# power_PCB.net
KiCad netlist of a schematic drawn in EAGLE
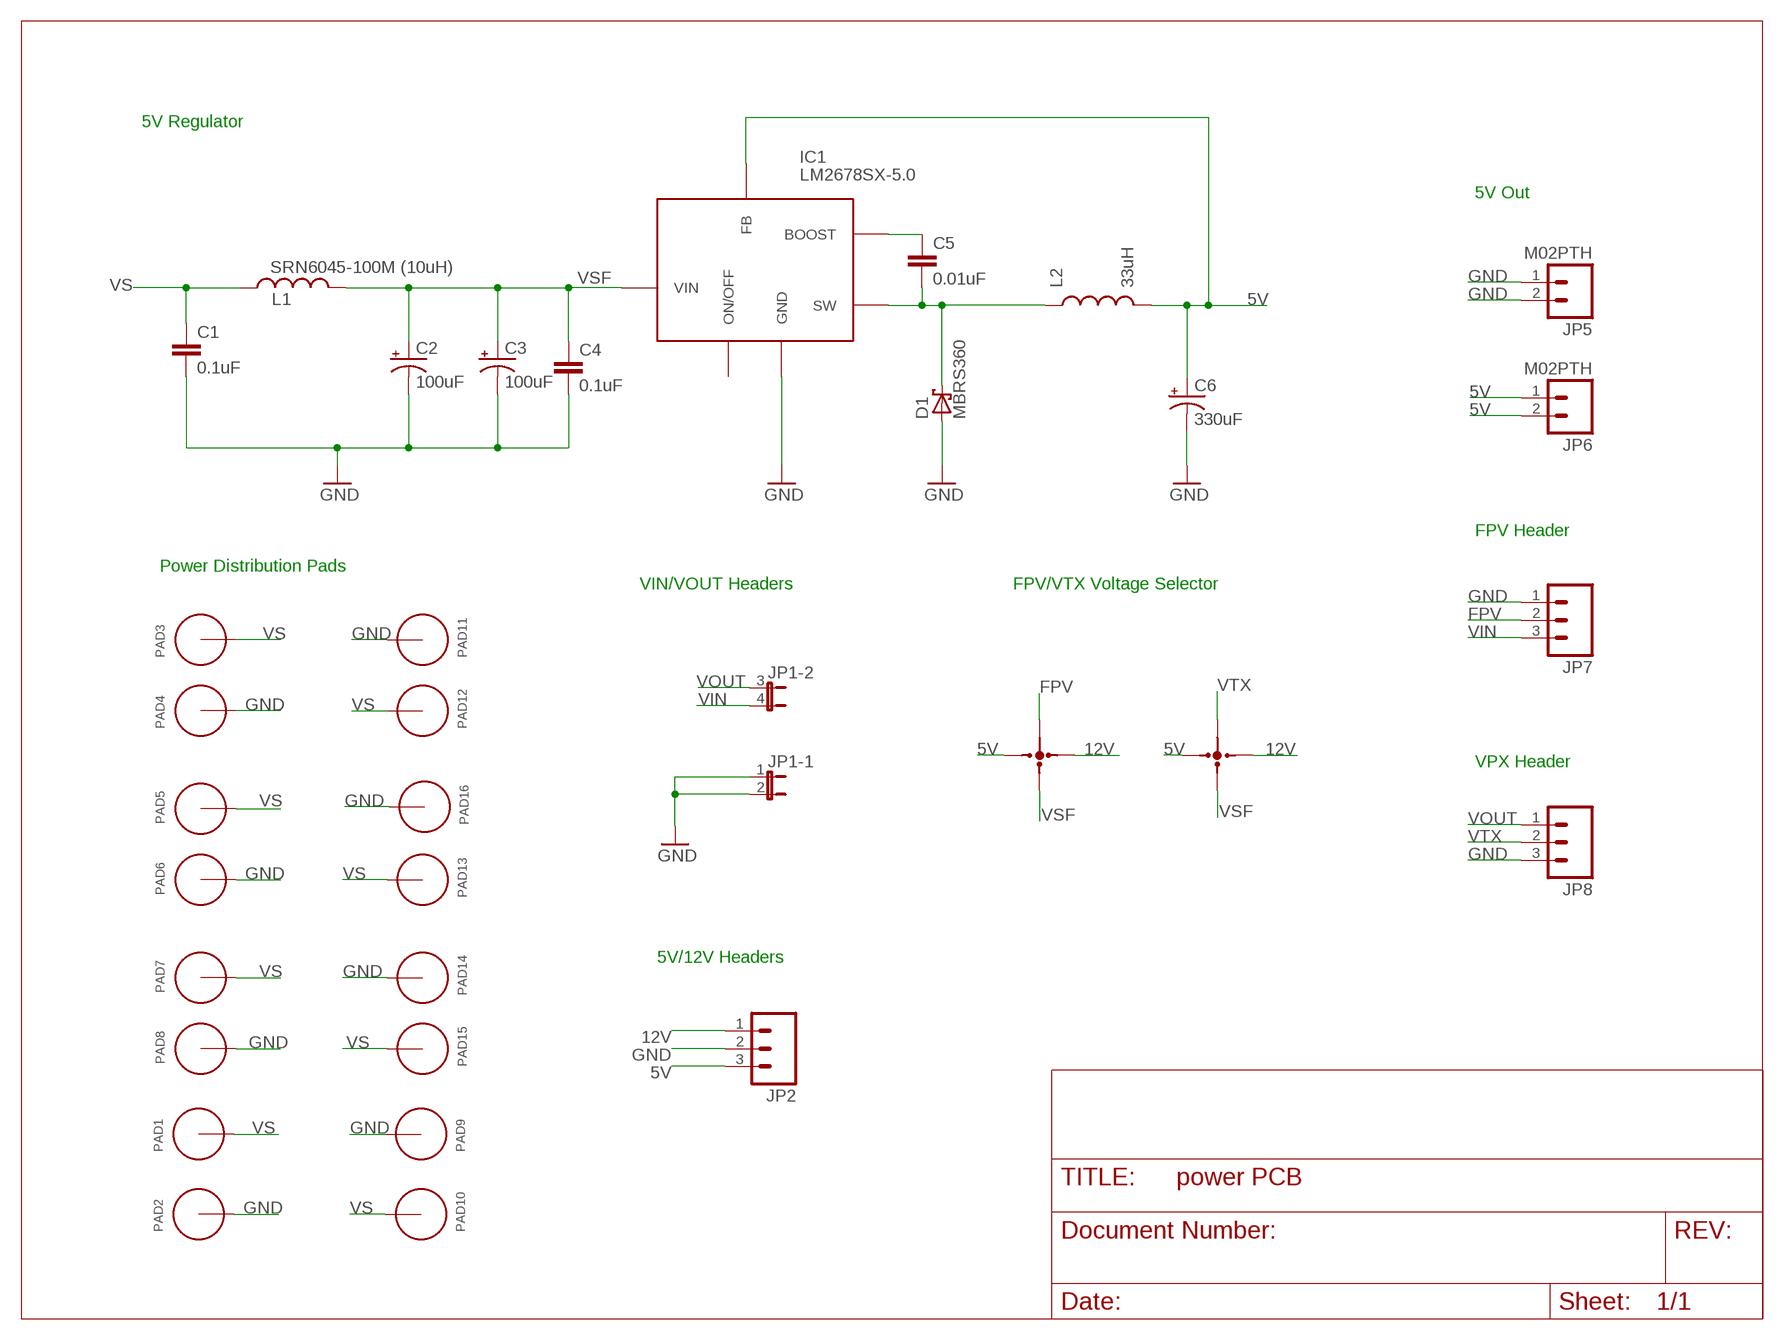
[diagram p0: schematic, sheet 1]

(export (version "E")
  (design (tool "Eeschema 10.0.6"))
  (components
    (comp (ref "C1")
      (value "0.1uF")
      (footprint "eagle-import:0603-CAP")
      (fields (field (name "PROD_ID") "CAP-00810"))
      (libsource (lib "eagle-import") (part "0.1UF-25V(+80/-20%)(0603)"))
    )
    (comp (ref "C2")
      (value "100uF")
      (footprint "eagle-import:EIA7343")
      (libsource (lib "eagle-import") (part "100UF-10V-10%(TANT)"))
    )
    (comp (ref "C3")
      (value "100uF")
      (footprint "eagle-import:EIA7343")
      (libsource (lib "eagle-import") (part "100UF-10V-10%(TANT)"))
    )
    (comp (ref "C4")
      (value "0.1uF")
      (footprint "eagle-import:0603-CAP")
      (libsource (lib "eagle-import") (part "0.1UF-25V(+80/-20%)(0603)"))
    )
    (comp (ref "C5")
      (value "0.01uF")
      (footprint "eagle-import:0603-CAP")
      (libsource (lib "eagle-import") (part "0.1UF-25V(+80/-20%)(0603)"))
    )
    (comp (ref "C6")
      (value "330uF")
      (footprint "eagle-import:EIA7343")
      (libsource (lib "eagle-import") (part "SparkFun-Capacitors_100UF-10V-10%(TANT)"))
    )
    (comp (ref "D1")
      (value "MBRS360")
      (footprint "eagle-import:SMB")
      (libsource (lib "eagle-import") (part "MBRS130LT3"))
    )
    (comp (ref "IC1")
      (value "LM2678SX-5.0")
      (footprint "eagle-import:P-TO263-7-1")
      (libsource (lib "eagle-import") (part "LM2678DX-5.0SX-5.0"))
    )
    (comp (ref "JP1")
      (value "JP2QE")
      (footprint "eagle-import:JP2Q")
      (libsource (lib "eagle-import") (part "JP2QE"))
    )
    (comp (ref "JP2")
      (value "M03PTH")
      (footprint "eagle-import:1X03")
      (libsource (lib "eagle-import") (part "M03PTH"))
    )
    (comp (ref "JP3")
      (value "3WAY_SMD_JUMPER")
      (footprint "eagle-import:3WAY_JUMPER")
      (libsource (lib "eagle-import") (part "3WAY_SMD_JUMPER"))
    )
    (comp (ref "JP4")
      (value "3WAY_SMD_JUMPER")
      (footprint "eagle-import:3WAY_JUMPER")
      (libsource (lib "eagle-import") (part "3WAY_SMD_JUMPER"))
    )
    (comp (ref "JP5")
      (value "M02PTH")
      (footprint "eagle-import:1X02")
      (libsource (lib "eagle-import") (part "M02PTH"))
    )
    (comp (ref "JP6")
      (value "M02PTH")
      (footprint "eagle-import:1X02")
      (libsource (lib "eagle-import") (part "M02PTH"))
    )
    (comp (ref "JP7")
      (value "M03PTH")
      (footprint "eagle-import:1X03")
      (libsource (lib "eagle-import") (part "M03PTH"))
    )
    (comp (ref "JP8")
      (value "M03PTH")
      (footprint "eagle-import:1X03")
      (libsource (lib "eagle-import") (part "M03PTH"))
    )
    (comp (ref "L1")
      (value "SRN6045-100M (10uH)")
      (footprint "eagle-import:SRN6045")
      (libsource (lib "eagle-import") (part "INDUCTORBOURNS_SRN6045"))
    )
    (comp (ref "L2")
      (value "33uH")
      (footprint "eagle-import:SRN6045")
      (libsource (lib "eagle-import") (part "INDUCTORBOURNS_SRN6045"))
    )
    (comp (ref "PAD1")
      (value "PAD_3MM")
      (footprint "eagle-import:PAD_3MM")
      (libsource (lib "eagle-import") (part "PAD_3MM"))
    )
    (comp (ref "PAD2")
      (value "PAD_3MM")
      (footprint "eagle-import:PAD_3MM")
      (libsource (lib "eagle-import") (part "PAD_3MM"))
    )
    (comp (ref "PAD3")
      (value "PAD_3MM")
      (footprint "eagle-import:PAD_3MM")
      (libsource (lib "eagle-import") (part "PAD_3MM"))
    )
    (comp (ref "PAD4")
      (value "PAD_3MM")
      (footprint "eagle-import:PAD_3MM")
      (libsource (lib "eagle-import") (part "PAD_3MM"))
    )
    (comp (ref "PAD5")
      (value "PAD_3MM")
      (footprint "eagle-import:PAD_3MM")
      (libsource (lib "eagle-import") (part "PAD_3MM"))
    )
    (comp (ref "PAD6")
      (value "PAD_3MM")
      (footprint "eagle-import:PAD_3MM")
      (libsource (lib "eagle-import") (part "PAD_3MM"))
    )
    (comp (ref "PAD7")
      (value "PAD_3MM")
      (footprint "eagle-import:PAD_3MM")
      (libsource (lib "eagle-import") (part "PAD_3MM"))
    )
    (comp (ref "PAD8")
      (value "PAD_3MM")
      (footprint "eagle-import:PAD_3MM")
      (libsource (lib "eagle-import") (part "PAD_3MM"))
    )
    (comp (ref "PAD9")
      (value "PAD_3MM")
      (footprint "eagle-import:PAD_3MM")
      (libsource (lib "eagle-import") (part "PAD_3MM"))
    )
    (comp (ref "PAD10")
      (value "PAD_3MM")
      (footprint "eagle-import:PAD_3MM")
      (libsource (lib "eagle-import") (part "PAD_3MM"))
    )
    (comp (ref "PAD11")
      (value "PAD_3MM")
      (footprint "eagle-import:PAD_3MM")
      (libsource (lib "eagle-import") (part "PAD_3MM"))
    )
    (comp (ref "PAD12")
      (value "PAD_3MM")
      (footprint "eagle-import:PAD_3MM")
      (libsource (lib "eagle-import") (part "PAD_3MM"))
    )
    (comp (ref "PAD13")
      (value "PAD_3MM")
      (footprint "eagle-import:PAD_3MM")
      (libsource (lib "eagle-import") (part "PAD_3MM"))
    )
    (comp (ref "PAD14")
      (value "PAD_3MM")
      (footprint "eagle-import:PAD_3MM")
      (libsource (lib "eagle-import") (part "PAD_3MM"))
    )
    (comp (ref "PAD15")
      (value "PAD_3MM")
      (footprint "eagle-import:PAD_3MM")
      (libsource (lib "eagle-import") (part "PAD_3MM"))
    )
    (comp (ref "PAD16")
      (value "PAD_3MM")
      (footprint "eagle-import:PAD_3MM")
      (libsource (lib "eagle-import") (part "PAD_3MM"))
    )
  )
  (nets
    (net (code "1") (name "/5V") (class "Default")
      (node (ref "C6") (pin "A") (pinfunction "+_A") (pintype "passive"))
      (node (ref "IC1") (pin "6") (pinfunction "FB_6") (pintype "bidirectional"))
      (node (ref "JP2") (pin "3") (pinfunction "3_3") (pintype "passive"))
      (node (ref "JP3") (pin "1") (pinfunction "1_1") (pintype "bidirectional"))
      (node (ref "JP4") (pin "3") (pinfunction "3_3") (pintype "bidirectional"))
      (node (ref "JP6") (pin "1") (pinfunction "1_1") (pintype "passive"))
      (node (ref "JP6") (pin "2") (pinfunction "2_2") (pintype "passive"))
      (node (ref "L2") (pin "2") (pinfunction "2_2") (pintype "passive"))
    )
    (net (code "2") (name "/12V") (class "Default")
      (node (ref "JP2") (pin "1") (pinfunction "1_1") (pintype "passive"))
      (node (ref "JP3") (pin "3") (pinfunction "3_3") (pintype "bidirectional"))
      (node (ref "JP4") (pin "1") (pinfunction "1_1") (pintype "bidirectional"))
    )
    (net (code "3") (name "/FPV") (class "Default")
      (node (ref "JP3") (pin "4") (pinfunction "4_4") (pintype "bidirectional"))
      (node (ref "JP7") (pin "2") (pinfunction "2_2") (pintype "passive"))
    )
    (net (code "4") (name "/VIN") (class "Default")
      (node (ref "JP1") (pin "4") (pinfunction "2_4") (pintype "passive"))
      (node (ref "JP7") (pin "3") (pinfunction "3_3") (pintype "passive"))
    )
    (net (code "5") (name "/VOUT") (class "Default")
      (node (ref "JP1") (pin "3") (pinfunction "1_3") (pintype "passive"))
      (node (ref "JP8") (pin "1") (pinfunction "1_1") (pintype "passive"))
    )
    (net (code "6") (name "/VS") (class "Default")
      (node (ref "C1") (pin "1") (pinfunction "1_1") (pintype "passive"))
      (node (ref "L1") (pin "1") (pinfunction "1_1") (pintype "passive"))
      (node (ref "PAD1") (pin "P$1") (pinfunction "1_P$1") (pintype "bidirectional"))
      (node (ref "PAD1") (pin "P$2") (pinfunction "1_P$2") (pintype "bidirectional"))
      (node (ref "PAD1") (pin "P$3") (pinfunction "1_P$3") (pintype "bidirectional"))
      (node (ref "PAD1") (pin "P$4") (pinfunction "1_P$4") (pintype "bidirectional"))
      (node (ref "PAD1") (pin "P$5") (pinfunction "1_P$5") (pintype "bidirectional"))
      (node (ref "PAD1") (pin "P$6") (pinfunction "1_P$6") (pintype "bidirectional"))
      (node (ref "PAD1") (pin "P$7") (pinfunction "1_P$7") (pintype "bidirectional"))
      (node (ref "PAD1") (pin "P$8") (pinfunction "1_P$8") (pintype "bidirectional"))
      (node (ref "PAD1") (pin "P$9") (pinfunction "1_P$9") (pintype "bidirectional"))
      (node (ref "PAD10") (pin "P$1") (pinfunction "1_P$1") (pintype "bidirectional"))
      (node (ref "PAD10") (pin "P$2") (pinfunction "1_P$2") (pintype "bidirectional"))
      (node (ref "PAD10") (pin "P$3") (pinfunction "1_P$3") (pintype "bidirectional"))
      (node (ref "PAD10") (pin "P$4") (pinfunction "1_P$4") (pintype "bidirectional"))
      (node (ref "PAD10") (pin "P$5") (pinfunction "1_P$5") (pintype "bidirectional"))
      (node (ref "PAD10") (pin "P$6") (pinfunction "1_P$6") (pintype "bidirectional"))
      (node (ref "PAD10") (pin "P$7") (pinfunction "1_P$7") (pintype "bidirectional"))
      (node (ref "PAD10") (pin "P$8") (pinfunction "1_P$8") (pintype "bidirectional"))
      (node (ref "PAD10") (pin "P$9") (pinfunction "1_P$9") (pintype "bidirectional"))
      (node (ref "PAD12") (pin "P$1") (pinfunction "1_P$1") (pintype "bidirectional"))
      (node (ref "PAD12") (pin "P$2") (pinfunction "1_P$2") (pintype "bidirectional"))
      (node (ref "PAD12") (pin "P$3") (pinfunction "1_P$3") (pintype "bidirectional"))
      (node (ref "PAD12") (pin "P$4") (pinfunction "1_P$4") (pintype "bidirectional"))
      (node (ref "PAD12") (pin "P$5") (pinfunction "1_P$5") (pintype "bidirectional"))
      (node (ref "PAD12") (pin "P$6") (pinfunction "1_P$6") (pintype "bidirectional"))
      (node (ref "PAD12") (pin "P$7") (pinfunction "1_P$7") (pintype "bidirectional"))
      (node (ref "PAD12") (pin "P$8") (pinfunction "1_P$8") (pintype "bidirectional"))
      (node (ref "PAD12") (pin "P$9") (pinfunction "1_P$9") (pintype "bidirectional"))
      (node (ref "PAD13") (pin "P$1") (pinfunction "1_P$1") (pintype "bidirectional"))
      (node (ref "PAD13") (pin "P$2") (pinfunction "1_P$2") (pintype "bidirectional"))
      (node (ref "PAD13") (pin "P$3") (pinfunction "1_P$3") (pintype "bidirectional"))
      (node (ref "PAD13") (pin "P$4") (pinfunction "1_P$4") (pintype "bidirectional"))
      (node (ref "PAD13") (pin "P$5") (pinfunction "1_P$5") (pintype "bidirectional"))
      (node (ref "PAD13") (pin "P$6") (pinfunction "1_P$6") (pintype "bidirectional"))
      (node (ref "PAD13") (pin "P$7") (pinfunction "1_P$7") (pintype "bidirectional"))
      (node (ref "PAD13") (pin "P$8") (pinfunction "1_P$8") (pintype "bidirectional"))
      (node (ref "PAD13") (pin "P$9") (pinfunction "1_P$9") (pintype "bidirectional"))
      (node (ref "PAD15") (pin "P$1") (pinfunction "1_P$1") (pintype "bidirectional"))
      (node (ref "PAD15") (pin "P$2") (pinfunction "1_P$2") (pintype "bidirectional"))
      (node (ref "PAD15") (pin "P$3") (pinfunction "1_P$3") (pintype "bidirectional"))
      (node (ref "PAD15") (pin "P$4") (pinfunction "1_P$4") (pintype "bidirectional"))
      (node (ref "PAD15") (pin "P$5") (pinfunction "1_P$5") (pintype "bidirectional"))
      (node (ref "PAD15") (pin "P$6") (pinfunction "1_P$6") (pintype "bidirectional"))
      (node (ref "PAD15") (pin "P$7") (pinfunction "1_P$7") (pintype "bidirectional"))
      (node (ref "PAD15") (pin "P$8") (pinfunction "1_P$8") (pintype "bidirectional"))
      (node (ref "PAD15") (pin "P$9") (pinfunction "1_P$9") (pintype "bidirectional"))
      (node (ref "PAD3") (pin "P$1") (pinfunction "1_P$1") (pintype "bidirectional"))
      (node (ref "PAD3") (pin "P$2") (pinfunction "1_P$2") (pintype "bidirectional"))
      (node (ref "PAD3") (pin "P$3") (pinfunction "1_P$3") (pintype "bidirectional"))
      (node (ref "PAD3") (pin "P$4") (pinfunction "1_P$4") (pintype "bidirectional"))
      (node (ref "PAD3") (pin "P$5") (pinfunction "1_P$5") (pintype "bidirectional"))
      (node (ref "PAD3") (pin "P$6") (pinfunction "1_P$6") (pintype "bidirectional"))
      (node (ref "PAD3") (pin "P$7") (pinfunction "1_P$7") (pintype "bidirectional"))
      (node (ref "PAD3") (pin "P$8") (pinfunction "1_P$8") (pintype "bidirectional"))
      (node (ref "PAD3") (pin "P$9") (pinfunction "1_P$9") (pintype "bidirectional"))
      (node (ref "PAD5") (pin "P$1") (pinfunction "1_P$1") (pintype "bidirectional"))
      (node (ref "PAD5") (pin "P$2") (pinfunction "1_P$2") (pintype "bidirectional"))
      (node (ref "PAD5") (pin "P$3") (pinfunction "1_P$3") (pintype "bidirectional"))
      (node (ref "PAD5") (pin "P$4") (pinfunction "1_P$4") (pintype "bidirectional"))
      (node (ref "PAD5") (pin "P$5") (pinfunction "1_P$5") (pintype "bidirectional"))
      (node (ref "PAD5") (pin "P$6") (pinfunction "1_P$6") (pintype "bidirectional"))
      (node (ref "PAD5") (pin "P$7") (pinfunction "1_P$7") (pintype "bidirectional"))
      (node (ref "PAD5") (pin "P$8") (pinfunction "1_P$8") (pintype "bidirectional"))
      (node (ref "PAD5") (pin "P$9") (pinfunction "1_P$9") (pintype "bidirectional"))
      (node (ref "PAD7") (pin "P$1") (pinfunction "1_P$1") (pintype "bidirectional"))
      (node (ref "PAD7") (pin "P$2") (pinfunction "1_P$2") (pintype "bidirectional"))
      (node (ref "PAD7") (pin "P$3") (pinfunction "1_P$3") (pintype "bidirectional"))
      (node (ref "PAD7") (pin "P$4") (pinfunction "1_P$4") (pintype "bidirectional"))
      (node (ref "PAD7") (pin "P$5") (pinfunction "1_P$5") (pintype "bidirectional"))
      (node (ref "PAD7") (pin "P$6") (pinfunction "1_P$6") (pintype "bidirectional"))
      (node (ref "PAD7") (pin "P$7") (pinfunction "1_P$7") (pintype "bidirectional"))
      (node (ref "PAD7") (pin "P$8") (pinfunction "1_P$8") (pintype "bidirectional"))
      (node (ref "PAD7") (pin "P$9") (pinfunction "1_P$9") (pintype "bidirectional"))
    )
    (net (code "7") (name "/VSF") (class "Default")
      (node (ref "C2") (pin "A") (pinfunction "+_A") (pintype "passive"))
      (node (ref "C3") (pin "A") (pinfunction "+_A") (pintype "passive"))
      (node (ref "C4") (pin "1") (pinfunction "1_1") (pintype "passive"))
      (node (ref "IC1") (pin "2") (pinfunction "VIN_2") (pintype "bidirectional"))
      (node (ref "JP3") (pin "2") (pinfunction "2_2") (pintype "bidirectional"))
      (node (ref "JP4") (pin "2") (pinfunction "2_2") (pintype "bidirectional"))
      (node (ref "L1") (pin "2") (pinfunction "2_2") (pintype "passive"))
    )
    (net (code "8") (name "/VTX") (class "Default")
      (node (ref "JP4") (pin "4") (pinfunction "4_4") (pintype "bidirectional"))
      (node (ref "JP8") (pin "2") (pinfunction "2_2") (pintype "passive"))
    )
    (net (code "9") (name "GND") (class "Default")
      (node (ref "C1") (pin "2") (pinfunction "2_2") (pintype "passive"))
      (node (ref "C2") (pin "C") (pinfunction "-_C") (pintype "passive"))
      (node (ref "C3") (pin "C") (pinfunction "-_C") (pintype "passive"))
      (node (ref "C4") (pin "2") (pinfunction "2_2") (pintype "passive"))
      (node (ref "C6") (pin "C") (pinfunction "-_C") (pintype "passive"))
      (node (ref "D1") (pin "A") (pinfunction "A_A") (pintype "passive"))
      (node (ref "IC1") (pin "4") (pinfunction "GND_4") (pintype "bidirectional"))
      (node (ref "IC1") (pin "TH") (pinfunction "GND_TH") (pintype "bidirectional"))
      (node (ref "JP1") (pin "1") (pinfunction "1_1") (pintype "passive"))
      (node (ref "JP1") (pin "2") (pinfunction "2_2") (pintype "passive"))
      (node (ref "JP2") (pin "2") (pinfunction "2_2") (pintype "passive"))
      (node (ref "JP5") (pin "1") (pinfunction "1_1") (pintype "passive"))
      (node (ref "JP5") (pin "2") (pinfunction "2_2") (pintype "passive"))
      (node (ref "JP7") (pin "1") (pinfunction "1_1") (pintype "passive"))
      (node (ref "JP8") (pin "3") (pinfunction "3_3") (pintype "passive"))
      (node (ref "PAD11") (pin "P$1") (pinfunction "1_P$1") (pintype "bidirectional"))
      (node (ref "PAD11") (pin "P$2") (pinfunction "1_P$2") (pintype "bidirectional"))
      (node (ref "PAD11") (pin "P$3") (pinfunction "1_P$3") (pintype "bidirectional"))
      (node (ref "PAD11") (pin "P$4") (pinfunction "1_P$4") (pintype "bidirectional"))
      (node (ref "PAD11") (pin "P$5") (pinfunction "1_P$5") (pintype "bidirectional"))
      (node (ref "PAD11") (pin "P$6") (pinfunction "1_P$6") (pintype "bidirectional"))
      (node (ref "PAD11") (pin "P$7") (pinfunction "1_P$7") (pintype "bidirectional"))
      (node (ref "PAD11") (pin "P$8") (pinfunction "1_P$8") (pintype "bidirectional"))
      (node (ref "PAD11") (pin "P$9") (pinfunction "1_P$9") (pintype "bidirectional"))
      (node (ref "PAD14") (pin "P$1") (pinfunction "1_P$1") (pintype "bidirectional"))
      (node (ref "PAD14") (pin "P$2") (pinfunction "1_P$2") (pintype "bidirectional"))
      (node (ref "PAD14") (pin "P$3") (pinfunction "1_P$3") (pintype "bidirectional"))
      (node (ref "PAD14") (pin "P$4") (pinfunction "1_P$4") (pintype "bidirectional"))
      (node (ref "PAD14") (pin "P$5") (pinfunction "1_P$5") (pintype "bidirectional"))
      (node (ref "PAD14") (pin "P$6") (pinfunction "1_P$6") (pintype "bidirectional"))
      (node (ref "PAD14") (pin "P$7") (pinfunction "1_P$7") (pintype "bidirectional"))
      (node (ref "PAD14") (pin "P$8") (pinfunction "1_P$8") (pintype "bidirectional"))
      (node (ref "PAD14") (pin "P$9") (pinfunction "1_P$9") (pintype "bidirectional"))
      (node (ref "PAD16") (pin "P$1") (pinfunction "1_P$1") (pintype "bidirectional"))
      (node (ref "PAD16") (pin "P$2") (pinfunction "1_P$2") (pintype "bidirectional"))
      (node (ref "PAD16") (pin "P$3") (pinfunction "1_P$3") (pintype "bidirectional"))
      (node (ref "PAD16") (pin "P$4") (pinfunction "1_P$4") (pintype "bidirectional"))
      (node (ref "PAD16") (pin "P$5") (pinfunction "1_P$5") (pintype "bidirectional"))
      (node (ref "PAD16") (pin "P$6") (pinfunction "1_P$6") (pintype "bidirectional"))
      (node (ref "PAD16") (pin "P$7") (pinfunction "1_P$7") (pintype "bidirectional"))
      (node (ref "PAD16") (pin "P$8") (pinfunction "1_P$8") (pintype "bidirectional"))
      (node (ref "PAD16") (pin "P$9") (pinfunction "1_P$9") (pintype "bidirectional"))
      (node (ref "PAD2") (pin "P$1") (pinfunction "1_P$1") (pintype "bidirectional"))
      (node (ref "PAD2") (pin "P$2") (pinfunction "1_P$2") (pintype "bidirectional"))
      (node (ref "PAD2") (pin "P$3") (pinfunction "1_P$3") (pintype "bidirectional"))
      (node (ref "PAD2") (pin "P$4") (pinfunction "1_P$4") (pintype "bidirectional"))
      (node (ref "PAD2") (pin "P$5") (pinfunction "1_P$5") (pintype "bidirectional"))
      (node (ref "PAD2") (pin "P$6") (pinfunction "1_P$6") (pintype "bidirectional"))
      (node (ref "PAD2") (pin "P$7") (pinfunction "1_P$7") (pintype "bidirectional"))
      (node (ref "PAD2") (pin "P$8") (pinfunction "1_P$8") (pintype "bidirectional"))
      (node (ref "PAD2") (pin "P$9") (pinfunction "1_P$9") (pintype "bidirectional"))
      (node (ref "PAD4") (pin "P$1") (pinfunction "1_P$1") (pintype "bidirectional"))
      (node (ref "PAD4") (pin "P$2") (pinfunction "1_P$2") (pintype "bidirectional"))
      (node (ref "PAD4") (pin "P$3") (pinfunction "1_P$3") (pintype "bidirectional"))
      (node (ref "PAD4") (pin "P$4") (pinfunction "1_P$4") (pintype "bidirectional"))
      (node (ref "PAD4") (pin "P$5") (pinfunction "1_P$5") (pintype "bidirectional"))
      (node (ref "PAD4") (pin "P$6") (pinfunction "1_P$6") (pintype "bidirectional"))
      (node (ref "PAD4") (pin "P$7") (pinfunction "1_P$7") (pintype "bidirectional"))
      (node (ref "PAD4") (pin "P$8") (pinfunction "1_P$8") (pintype "bidirectional"))
      (node (ref "PAD4") (pin "P$9") (pinfunction "1_P$9") (pintype "bidirectional"))
      (node (ref "PAD6") (pin "P$1") (pinfunction "1_P$1") (pintype "bidirectional"))
      (node (ref "PAD6") (pin "P$2") (pinfunction "1_P$2") (pintype "bidirectional"))
      (node (ref "PAD6") (pin "P$3") (pinfunction "1_P$3") (pintype "bidirectional"))
      (node (ref "PAD6") (pin "P$4") (pinfunction "1_P$4") (pintype "bidirectional"))
      (node (ref "PAD6") (pin "P$5") (pinfunction "1_P$5") (pintype "bidirectional"))
      (node (ref "PAD6") (pin "P$6") (pinfunction "1_P$6") (pintype "bidirectional"))
      (node (ref "PAD6") (pin "P$7") (pinfunction "1_P$7") (pintype "bidirectional"))
      (node (ref "PAD6") (pin "P$8") (pinfunction "1_P$8") (pintype "bidirectional"))
      (node (ref "PAD6") (pin "P$9") (pinfunction "1_P$9") (pintype "bidirectional"))
      (node (ref "PAD8") (pin "P$1") (pinfunction "1_P$1") (pintype "bidirectional"))
      (node (ref "PAD8") (pin "P$2") (pinfunction "1_P$2") (pintype "bidirectional"))
      (node (ref "PAD8") (pin "P$3") (pinfunction "1_P$3") (pintype "bidirectional"))
      (node (ref "PAD8") (pin "P$4") (pinfunction "1_P$4") (pintype "bidirectional"))
      (node (ref "PAD8") (pin "P$5") (pinfunction "1_P$5") (pintype "bidirectional"))
      (node (ref "PAD8") (pin "P$6") (pinfunction "1_P$6") (pintype "bidirectional"))
      (node (ref "PAD8") (pin "P$7") (pinfunction "1_P$7") (pintype "bidirectional"))
      (node (ref "PAD8") (pin "P$8") (pinfunction "1_P$8") (pintype "bidirectional"))
      (node (ref "PAD8") (pin "P$9") (pinfunction "1_P$9") (pintype "bidirectional"))
      (node (ref "PAD9") (pin "P$1") (pinfunction "1_P$1") (pintype "bidirectional"))
      (node (ref "PAD9") (pin "P$2") (pinfunction "1_P$2") (pintype "bidirectional"))
      (node (ref "PAD9") (pin "P$3") (pinfunction "1_P$3") (pintype "bidirectional"))
      (node (ref "PAD9") (pin "P$4") (pinfunction "1_P$4") (pintype "bidirectional"))
      (node (ref "PAD9") (pin "P$5") (pinfunction "1_P$5") (pintype "bidirectional"))
      (node (ref "PAD9") (pin "P$6") (pinfunction "1_P$6") (pintype "bidirectional"))
      (node (ref "PAD9") (pin "P$7") (pinfunction "1_P$7") (pintype "bidirectional"))
      (node (ref "PAD9") (pin "P$8") (pinfunction "1_P$8") (pintype "bidirectional"))
      (node (ref "PAD9") (pin "P$9") (pinfunction "1_P$9") (pintype "bidirectional"))
    )
    (net (code "10") (name "Net-(IC1-BOOST)") (class "Default")
      (node (ref "C5") (pin "1") (pinfunction "1_1") (pintype "passive"))
      (node (ref "IC1") (pin "3") (pinfunction "BOOST_3") (pintype "bidirectional"))
    )
    (net (code "11") (name "Net-(IC1-SW)") (class "Default")
      (node (ref "C5") (pin "2") (pinfunction "2_2") (pintype "passive"))
      (node (ref "D1") (pin "C") (pinfunction "C_C") (pintype "passive"))
      (node (ref "IC1") (pin "1") (pinfunction "SW_1") (pintype "bidirectional"))
      (node (ref "L2") (pin "1") (pinfunction "1_1") (pintype "passive"))
    )
    (net (code "12") (name "unconnected-(IC1-ON{slash}OFF-Pad7)") (class "Default")
      (node (ref "IC1") (pin "7") (pinfunction "ON/OFF_7") (pintype "bidirectional"))
    )
  )
)
